# samd21g_board.net
KiCad netlist of a schematic drawn in EAGLE
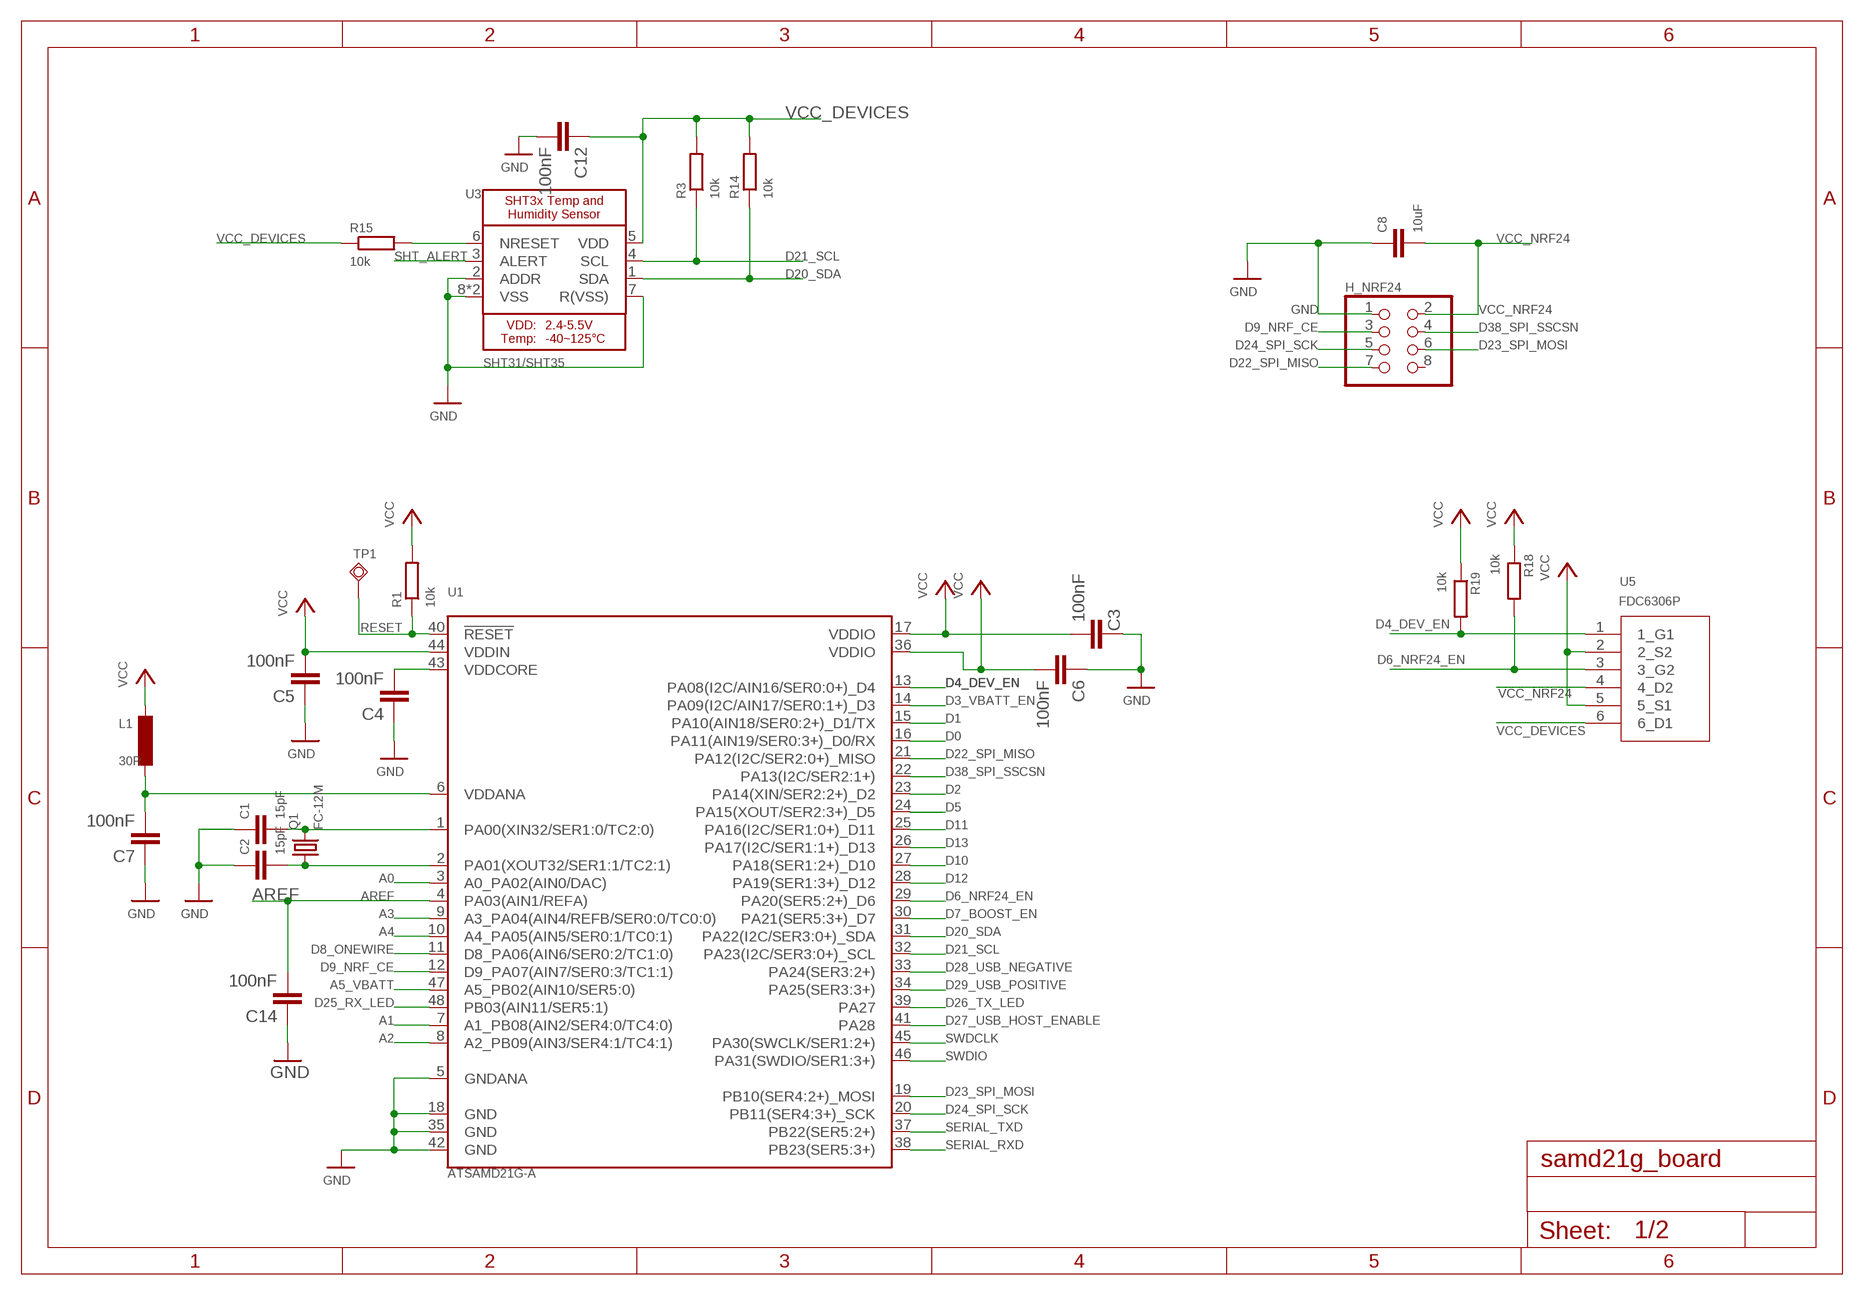
[diagram p0: schematic, sheet 1]
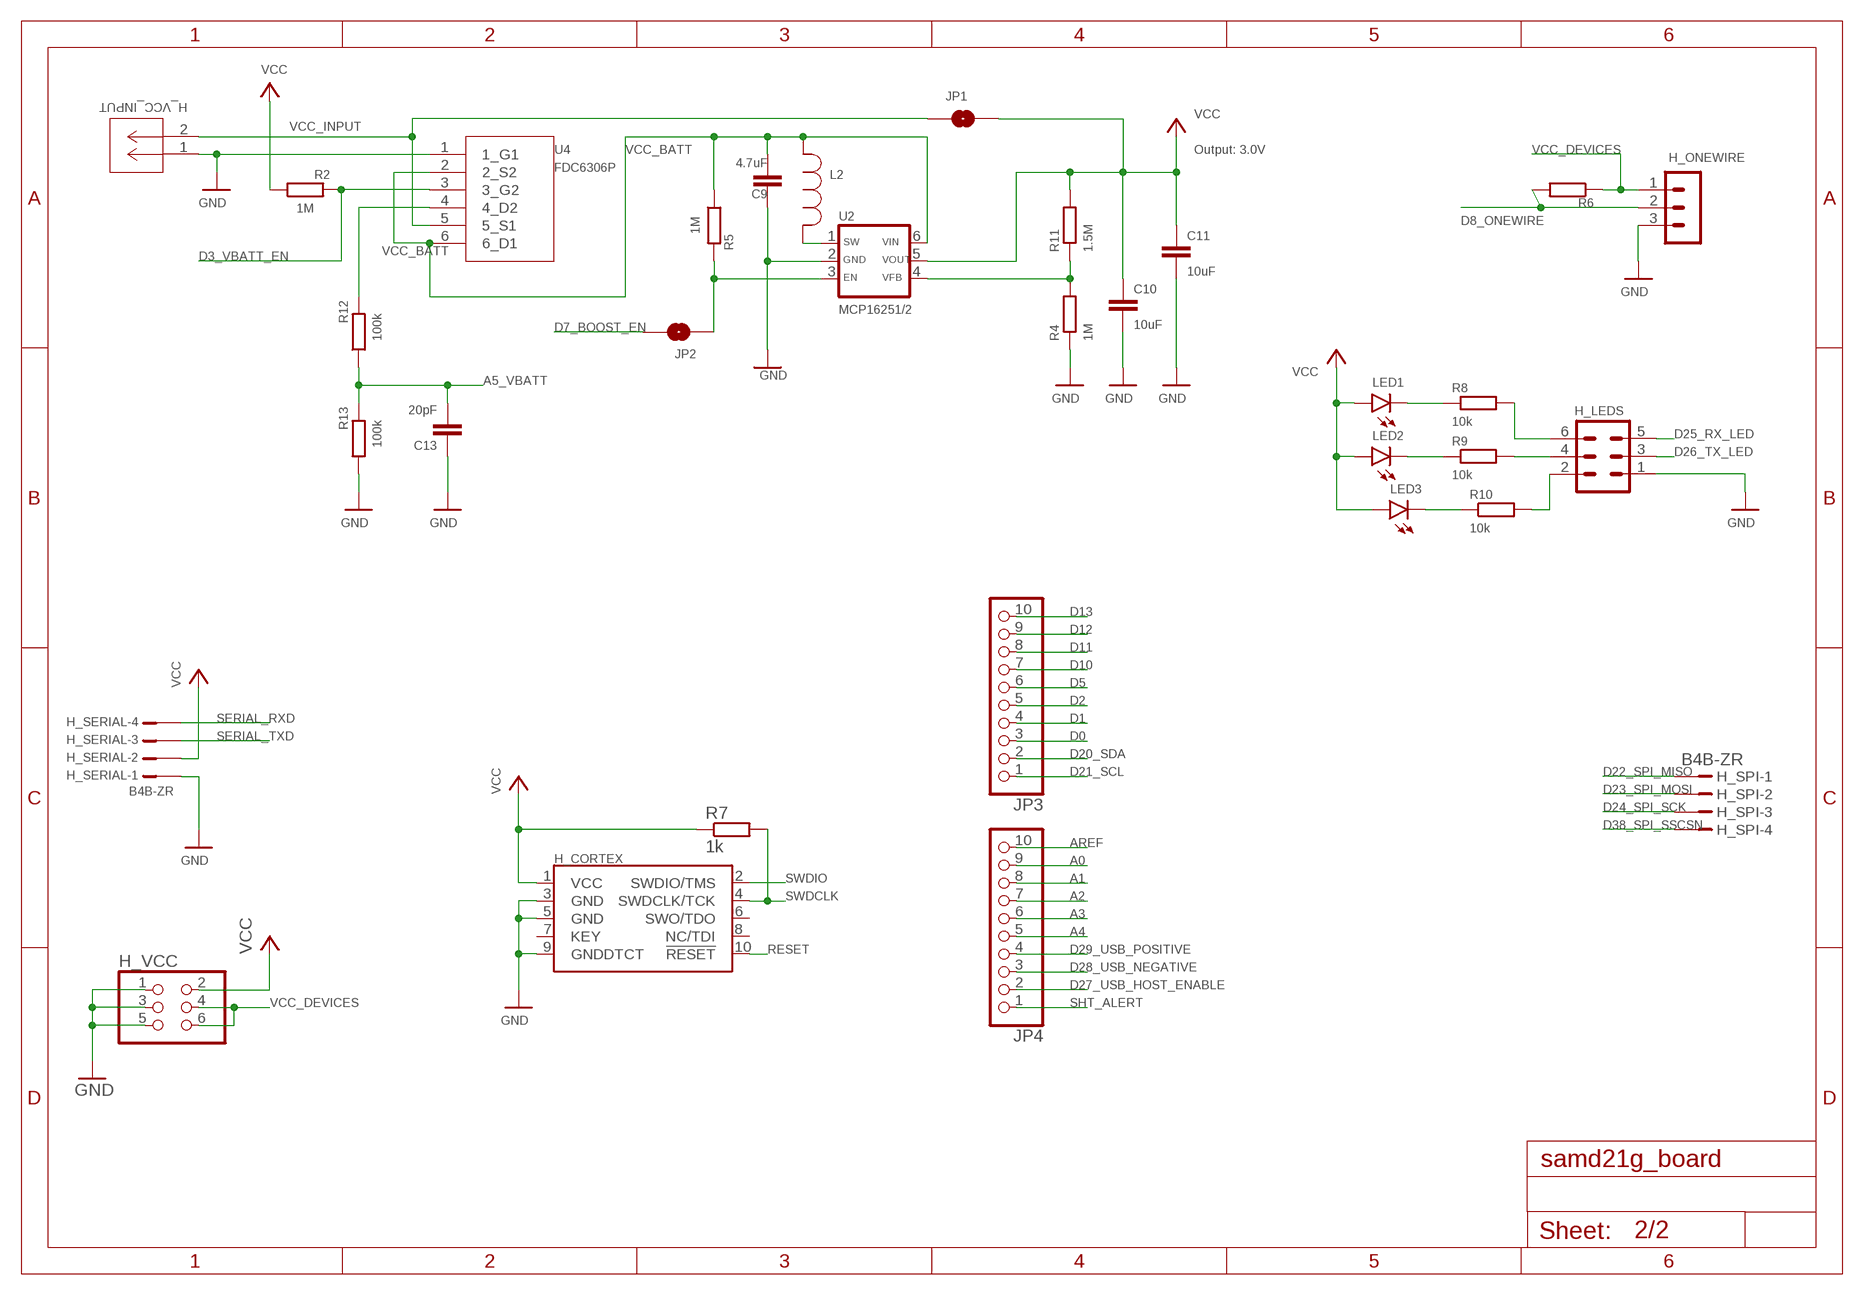
[diagram p1: schematic, sheet 2]

(export (version "E")
  (design (tool "Eeschema 10.0.6"))
  (components
    (comp (ref "C1")
      (value "15pF")
      (footprint "eagle-import:C0402")
      (libsource (lib "eagle-import") (part "C-EUC0402"))
    )
    (comp (ref "C2")
      (value "15pF")
      (footprint "eagle-import:C0402")
      (libsource (lib "eagle-import") (part "C-EUC0402"))
    )
    (comp (ref "C3")
      (value "100nF")
      (footprint "eagle-import:C0603")
      (libsource (lib "eagle-import") (part "C-EUC0603"))
    )
    (comp (ref "C4")
      (value "100nF")
      (footprint "eagle-import:C0603")
      (libsource (lib "eagle-import") (part "C-EUC0603"))
    )
    (comp (ref "C5")
      (value "100nF")
      (footprint "eagle-import:C0603")
      (libsource (lib "eagle-import") (part "C-EUC0603"))
    )
    (comp (ref "C6")
      (value "100nF")
      (footprint "eagle-import:C0603")
      (libsource (lib "eagle-import") (part "C-EUC0603"))
    )
    (comp (ref "C7")
      (value "100nF")
      (footprint "eagle-import:C0603")
      (libsource (lib "eagle-import") (part "C-EUC0603"))
    )
    (comp (ref "C8")
      (value "10uF")
      (footprint "eagle-import:C0805")
      (libsource (lib "eagle-import") (part "C-EUC0805"))
    )
    (comp (ref "C12")
      (value "100nF")
      (footprint "eagle-import:C0603")
      (libsource (lib "eagle-import") (part "C-EUC0603"))
    )
    (comp (ref "C14")
      (value "100nF")
      (footprint "eagle-import:C0603")
      (libsource (lib "eagle-import") (part "C-EUC0603"))
    )
    (comp (ref "H_NRF24")
      (value "PINHD-2X04_2.54")
      (footprint "eagle-import:2X04")
      (libsource (lib "eagle-import") (part "PINHD-2X04_2.54"))
    )
    (comp (ref "L1")
      (value "30R")
      (footprint "eagle-import:L3225M")
      (libsource (lib "eagle-import") (part "L-EUL3225M"))
    )
    (comp (ref "Q1")
      (value "FC-12M")
      (footprint "eagle-import:FC-12M")
      (libsource (lib "eagle-import") (part "FC-12M"))
    )
    (comp (ref "R1")
      (value "10k")
      (footprint "eagle-import:R0805")
      (libsource (lib "eagle-import") (part "R-EU_R0805"))
    )
    (comp (ref "R3")
      (value "10k")
      (footprint "eagle-import:R0805")
      (libsource (lib "eagle-import") (part "R-EU_R0805"))
    )
    (comp (ref "R14")
      (value "10k")
      (footprint "eagle-import:R0805")
      (libsource (lib "eagle-import") (part "R-EU_R0805"))
    )
    (comp (ref "R15")
      (value "10k")
      (footprint "eagle-import:R0805")
      (libsource (lib "eagle-import") (part "R-EU_R0805"))
    )
    (comp (ref "R18")
      (value "10k")
      (footprint "eagle-import:R0805")
      (libsource (lib "eagle-import") (part "R-EU_R0805"))
    )
    (comp (ref "R19")
      (value "10k")
      (footprint "eagle-import:R0805")
      (libsource (lib "eagle-import") (part "R-EU_R0805"))
    )
    (comp (ref "TP1")
      (value "TPSQTP13SQ")
      (footprint "eagle-import:TP13SQ")
      (libsource (lib "eagle-import") (part "TPSQTP13SQ"))
    )
    (comp (ref "U1")
      (value "ATSAMD21G-A")
      (footprint "eagle-import:TQFP-48")
      (libsource (lib "eagle-import") (part "ATSAMD21G-A"))
    )
    (comp (ref "U3")
      (value "SHT31/SHT35")
      (footprint "eagle-import:SHT3X_DFN8")
      (libsource (lib "eagle-import") (part "SHT3X"))
    )
    (comp (ref "U5")
      (value "FDC6306P")
      (footprint "eagle-import:TSOT23-6_419BL_ONS")
      (fields (field (name "COPYRIGHT") "Copyright (C) 2018 Accelerated Designs. All rights reserved"))
      (libsource (lib "eagle-import") (part "FDC6306P"))
    )
    (comp (ref "C9")
      (value "4.7uF")
      (footprint "eagle-import:C0805")
      (libsource (lib "eagle-import") (part "C-EUC0805"))
    )
    (comp (ref "C10")
      (value "10uF")
      (footprint "eagle-import:C0805")
      (libsource (lib "eagle-import") (part "C-EUC0805"))
    )
    (comp (ref "C11")
      (value "10uF")
      (footprint "eagle-import:C0805")
      (libsource (lib "eagle-import") (part "C-EUC0805"))
    )
    (comp (ref "C13")
      (value "20pF")
      (footprint "eagle-import:C0402")
      (libsource (lib "eagle-import") (part "C-EUC0402"))
    )
    (comp (ref "H_CORTEX")
      (value "CORTEX_JTAG_DEBUG_PTH")
      (footprint "eagle-import:2X5-PTH-1.27MM")
      (fields (field (name "SPICEPREFIX") "X"))
      (libsource (lib "eagle-import") (part "CORTEX_JTAG_DEBUG_PTH"))
    )
    (comp (ref "H_LEDS")
      (value "M_2R03_50MIL-V2")
      (footprint "eagle-import:M_2R03_50MIL-V2")
      (libsource (lib "eagle-import") (part "M_2R03_50MIL-V2"))
    )
    (comp (ref "H_ONEWIRE")
      (value "M_1R03_50MIL-V")
      (footprint "eagle-import:M_1R03_50MIL-V")
      (libsource (lib "eagle-import") (part "M_1R03_50MIL-V"))
    )
    (comp (ref "H_SERIAL")
      (value "B4B-ZR")
      (footprint "eagle-import:B4B-ZR")
      (fields (field (name "MF") "FARNELL") (field (name "MPN") "B4B-ZR(LF)(SN)"))
      (libsource (lib "eagle-import") (part "?4B-ZRB"))
    )
    (comp (ref "H_SPI")
      (value "B4B-ZR")
      (footprint "eagle-import:B4B-ZR")
      (fields (field (name "MF") "FARNELL") (field (name "MPN") "B4B-ZR(LF)(SN)"))
      (libsource (lib "eagle-import") (part "?4B-ZRB"))
    )
    (comp (ref "H_VCC")
      (value "PINHD-2X03_2.54")
      (footprint "eagle-import:2X03")
      (libsource (lib "eagle-import") (part "PINHD-2X03_2.54"))
    )
    (comp (ref "H_VCC_INPUT")
      (value "S2B-ZR")
      (footprint "eagle-import:CONN_S2B-ZR_JST")
      (fields
        (field (name "MANUFACTURER_PART_NUMBER") "S2B-ZR(LF)(SN)")
        (field (name "COPYRIGHT") "Copyright (C) 2018 Accelerated Designs. All rights reserved")
      )
      (libsource (lib "eagle-import") (part "S2B-ZR(LF)(SN)"))
    )
    (comp (ref "JP1")
      (value "JUMPER-SMT_2_NO_NO-SILK")
      (footprint "eagle-import:SMT-JUMPER_2_NO_NO-SILK")
      (libsource (lib "eagle-import") (part "JUMPER-SMT_2_NO_NO-SILK"))
    )
    (comp (ref "JP2")
      (value "JUMPER-SMT_2_NO_NO-SILK")
      (footprint "eagle-import:SMT-JUMPER_2_NO_NO-SILK")
      (libsource (lib "eagle-import") (part "JUMPER-SMT_2_NO_NO-SILK"))
    )
    (comp (ref "JP3")
      (value "PINHD-1X10_2.54-S")
      (footprint "eagle-import:1X10-S")
      (libsource (lib "eagle-import") (part "PINHD-1X10_2.54-S"))
    )
    (comp (ref "JP4")
      (value "PINHD-1X10_2.54-S")
      (footprint "eagle-import:1X10-S")
      (libsource (lib "eagle-import") (part "PINHD-1X10_2.54-S"))
    )
    (comp (ref "L2")
      (value "4.7uH")
      (footprint "eagle-import:IND_CDRH3D16-4R7NC_SUM")
      (fields
        (field (name "MANUFACTURER_PART_NUMBER") "CDRH3D16/HPNP-4R7NC")
        (field (name "COPYRIGHT") "Copyright (C) 2018 Accelerated Designs. All rights reserved")
      )
      (libsource (lib "eagle-import") (part "CDRH3D16-4R7NC"))
    )
    (comp (ref "LED1")
      (value "LEDCHIP-LED0805")
      (footprint "eagle-import:CHIP-LED0805")
      (libsource (lib "eagle-import") (part "LEDCHIP-LED0805"))
    )
    (comp (ref "LED2")
      (value "LEDCHIP-LED0805")
      (footprint "eagle-import:CHIP-LED0805")
      (libsource (lib "eagle-import") (part "LEDCHIP-LED0805"))
    )
    (comp (ref "LED3")
      (value "LEDCHIP-LED0805")
      (footprint "eagle-import:CHIP-LED0805")
      (libsource (lib "eagle-import") (part "LEDCHIP-LED0805"))
    )
    (comp (ref "R2")
      (value "1M")
      (footprint "eagle-import:R0805")
      (libsource (lib "eagle-import") (part "R-EU_R0805"))
    )
    (comp (ref "R4")
      (value "1M")
      (footprint "eagle-import:R0805")
      (libsource (lib "eagle-import") (part "R-EU_R0805"))
    )
    (comp (ref "R5")
      (value "1M")
      (footprint "eagle-import:R0805")
      (libsource (lib "eagle-import") (part "R-EU_R0805"))
    )
    (comp (ref "R6")
      (value "4.7k")
      (footprint "eagle-import:R0805")
      (libsource (lib "eagle-import") (part "R-EU_R0805"))
    )
    (comp (ref "R7")
      (value "1k")
      (footprint "eagle-import:R0805")
      (fields (field (name "SPICEPREFIX") "R"))
      (libsource (lib "eagle-import") (part "R-EU_R0805"))
    )
    (comp (ref "R8")
      (value "10k")
      (footprint "eagle-import:R0805")
      (libsource (lib "eagle-import") (part "R-EU_R0805"))
    )
    (comp (ref "R9")
      (value "10k")
      (footprint "eagle-import:R0805")
      (libsource (lib "eagle-import") (part "R-EU_R0805"))
    )
    (comp (ref "R10")
      (value "10k")
      (footprint "eagle-import:R0805")
      (libsource (lib "eagle-import") (part "R-EU_R0805"))
    )
    (comp (ref "R11")
      (value "1.5M")
      (footprint "eagle-import:R0805")
      (libsource (lib "eagle-import") (part "R-EU_R0805"))
    )
    (comp (ref "R12")
      (value "100k")
      (footprint "eagle-import:R0805")
      (libsource (lib "eagle-import") (part "R-EU_R0805"))
    )
    (comp (ref "R13")
      (value "100k")
      (footprint "eagle-import:R0805")
      (libsource (lib "eagle-import") (part "R-EU_R0805"))
    )
    (comp (ref "U2")
      (value "MCP16251/2")
      (footprint "eagle-import:SOT-23-6")
      (libsource (lib "eagle-import") (part "MCP16251/2"))
    )
    (comp (ref "U4")
      (value "FDC6306P")
      (footprint "eagle-import:TSOT23-6_419BL_ONS")
      (fields (field (name "COPYRIGHT") "Copyright (C) 2018 Accelerated Designs. All rights reserved"))
      (libsource (lib "eagle-import") (part "FDC6306P"))
    )
  )
  (nets
    (net (code "1") (name "A0") (class "Default")
      (node (ref "JP4") (pin "9") (pinfunction "9_9") (pintype "passive"))
      (node (ref "U1") (pin "3") (pinfunction "A0_PA02(AIN0/DAC)_3") (pintype "bidirectional"))
    )
    (net (code "2") (name "A1") (class "Default")
      (node (ref "JP4") (pin "8") (pinfunction "8_8") (pintype "passive"))
      (node (ref "U1") (pin "7") (pinfunction "A1_PB08(AIN2/SER4:0/TC4:0)_7") (pintype "bidirectional"))
    )
    (net (code "3") (name "A2") (class "Default")
      (node (ref "JP4") (pin "7") (pinfunction "7_7") (pintype "passive"))
      (node (ref "U1") (pin "8") (pinfunction "A2_PB09(AIN3/SER4:1/TC4:1)_8") (pintype "bidirectional"))
    )
    (net (code "4") (name "A3") (class "Default")
      (node (ref "JP4") (pin "6") (pinfunction "6_6") (pintype "passive"))
      (node (ref "U1") (pin "9") (pinfunction "A3_PA04(AIN4/REFB/SER0:0/TC0:0)_9") (pintype "bidirectional"))
    )
    (net (code "5") (name "A4") (class "Default")
      (node (ref "JP4") (pin "5") (pinfunction "5_5") (pintype "passive"))
      (node (ref "U1") (pin "10") (pinfunction "A4_PA05(AIN5/SER0:1/TC0:1)_10") (pintype "bidirectional"))
    )
    (net (code "6") (name "A5_VBATT") (class "Default")
      (node (ref "C13") (pin "2") (pinfunction "2_2") (pintype "passive"))
      (node (ref "R12") (pin "1") (pinfunction "1_1") (pintype "passive"))
      (node (ref "R13") (pin "2") (pinfunction "2_2") (pintype "passive"))
      (node (ref "U1") (pin "47") (pinfunction "A5_PB02(AIN10/SER5:0)_47") (pintype "bidirectional"))
    )
    (net (code "7") (name "AREF") (class "Default")
      (node (ref "C14") (pin "2") (pinfunction "2_2") (pintype "passive"))
      (node (ref "JP4") (pin "10") (pinfunction "10_10") (pintype "passive"))
      (node (ref "U1") (pin "4") (pinfunction "PA03(AIN1/REFA)_4") (pintype "bidirectional"))
    )
    (net (code "8") (name "D0") (class "Default")
      (node (ref "JP3") (pin "3") (pinfunction "3_3") (pintype "passive"))
      (node (ref "U1") (pin "16") (pinfunction "PA11(AIN19/SER0:3+)_D0/RX_16") (pintype "bidirectional"))
    )
    (net (code "9") (name "D1") (class "Default")
      (node (ref "JP3") (pin "4") (pinfunction "4_4") (pintype "passive"))
      (node (ref "U1") (pin "15") (pinfunction "PA10(AIN18/SER0:2+)_D1/TX_15") (pintype "bidirectional"))
    )
    (net (code "10") (name "D2") (class "Default")
      (node (ref "JP3") (pin "5") (pinfunction "5_5") (pintype "passive"))
      (node (ref "U1") (pin "23") (pinfunction "PA14(XIN/SER2:2+)_D2_23") (pintype "bidirectional"))
    )
    (net (code "11") (name "D3_VBATT_EN") (class "Default")
      (node (ref "R2") (pin "2") (pinfunction "2_2") (pintype "passive"))
      (node (ref "U1") (pin "14") (pinfunction "PA09(I2C/AIN17/SER0:1+)_D3_14") (pintype "bidirectional"))
      (node (ref "U4") (pin "3") (pinfunction "3_G2_3") (pintype "passive"))
    )
    (net (code "12") (name "D4_DEV_EN") (class "Default")
      (node (ref "R19") (pin "2") (pinfunction "2_2") (pintype "passive"))
      (node (ref "U1") (pin "13") (pinfunction "PA08(I2C/AIN16/SER0:0+)_D4_13") (pintype "bidirectional"))
      (node (ref "U5") (pin "1") (pinfunction "1_G1_1") (pintype "passive"))
    )
    (net (code "13") (name "D5") (class "Default")
      (node (ref "JP3") (pin "6") (pinfunction "6_6") (pintype "passive"))
      (node (ref "U1") (pin "24") (pinfunction "PA15(XOUT/SER2:3+)_D5_24") (pintype "bidirectional"))
    )
    (net (code "14") (name "D6_NRF24_EN") (class "Default")
      (node (ref "R18") (pin "2") (pinfunction "2_2") (pintype "passive"))
      (node (ref "U1") (pin "29") (pinfunction "PA20(SER5:2+)_D6_29") (pintype "bidirectional"))
      (node (ref "U5") (pin "3") (pinfunction "3_G2_3") (pintype "passive"))
    )
    (net (code "15") (name "D7_BOOST_EN") (class "Default")
      (node (ref "JP2") (pin "2") (pinfunction "2_2") (pintype "passive"))
      (node (ref "U1") (pin "30") (pinfunction "PA21(SER5:3+)_D7_30") (pintype "bidirectional"))
    )
    (net (code "16") (name "D8_ONEWIRE") (class "Default")
      (node (ref "H_ONEWIRE") (pin "2") (pinfunction "2_2") (pintype "bidirectional"))
      (node (ref "R6") (pin "2") (pinfunction "2_2") (pintype "passive"))
      (node (ref "U1") (pin "11") (pinfunction "D8_PA06(AIN6/SER0:2/TC1:0)_11") (pintype "bidirectional"))
    )
    (net (code "17") (name "D9_NRF_CE") (class "Default")
      (node (ref "H_NRF24") (pin "3") (pinfunction "3_3") (pintype "passive"))
      (node (ref "U1") (pin "12") (pinfunction "D9_PA07(AIN7/SER0:3/TC1:1)_12") (pintype "bidirectional"))
    )
    (net (code "18") (name "D10") (class "Default")
      (node (ref "JP3") (pin "7") (pinfunction "7_7") (pintype "passive"))
      (node (ref "U1") (pin "27") (pinfunction "PA18(SER1:2+)_D10_27") (pintype "bidirectional"))
    )
    (net (code "19") (name "D11") (class "Default")
      (node (ref "JP3") (pin "8") (pinfunction "8_8") (pintype "passive"))
      (node (ref "U1") (pin "25") (pinfunction "PA16(I2C/SER1:0+)_D11_25") (pintype "bidirectional"))
    )
    (net (code "20") (name "D12") (class "Default")
      (node (ref "JP3") (pin "9") (pinfunction "9_9") (pintype "passive"))
      (node (ref "U1") (pin "28") (pinfunction "PA19(SER1:3+)_D12_28") (pintype "bidirectional"))
    )
    (net (code "21") (name "D13") (class "Default")
      (node (ref "JP3") (pin "10") (pinfunction "10_10") (pintype "passive"))
      (node (ref "U1") (pin "26") (pinfunction "PA17(I2C/SER1:1+)_D13_26") (pintype "bidirectional"))
    )
    (net (code "22") (name "D20_SDA") (class "Default")
      (node (ref "JP3") (pin "2") (pinfunction "2_2") (pintype "passive"))
      (node (ref "R14") (pin "1") (pinfunction "1_1") (pintype "passive"))
      (node (ref "U1") (pin "31") (pinfunction "PA22(I2C/SER3:0+)_SDA_31") (pintype "bidirectional"))
      (node (ref "U3") (pin "1") (pinfunction "SDA_1") (pintype "bidirectional"))
    )
    (net (code "23") (name "D21_SCL") (class "Default")
      (node (ref "JP3") (pin "1") (pinfunction "1_1") (pintype "passive"))
      (node (ref "R3") (pin "1") (pinfunction "1_1") (pintype "passive"))
      (node (ref "U1") (pin "32") (pinfunction "PA23(I2C/SER3:0+)_SCL_32") (pintype "bidirectional"))
      (node (ref "U3") (pin "4") (pinfunction "SCL_4") (pintype "bidirectional"))
    )
    (net (code "24") (name "D22_SPI_MISO") (class "Default")
      (node (ref "H_NRF24") (pin "7") (pinfunction "7_7") (pintype "passive"))
      (node (ref "H_SPI") (pin "1") (pinfunction "1_1") (pintype "passive"))
      (node (ref "U1") (pin "21") (pinfunction "PA12(I2C/SER2:0+)_MISO_21") (pintype "bidirectional"))
    )
    (net (code "25") (name "D23_SPI_MOSI") (class "Default")
      (node (ref "H_NRF24") (pin "6") (pinfunction "6_6") (pintype "passive"))
      (node (ref "H_SPI") (pin "2") (pinfunction "1_2") (pintype "passive"))
      (node (ref "U1") (pin "19") (pinfunction "PB10(SER4:2+)_MOSI_19") (pintype "bidirectional"))
    )
    (net (code "26") (name "D24_SPI_SCK") (class "Default")
      (node (ref "H_NRF24") (pin "5") (pinfunction "5_5") (pintype "passive"))
      (node (ref "H_SPI") (pin "3") (pinfunction "1_3") (pintype "passive"))
      (node (ref "U1") (pin "20") (pinfunction "PB11(SER4:3+)_SCK_20") (pintype "bidirectional"))
    )
    (net (code "27") (name "D25_RX_LED") (class "Default")
      (node (ref "H_LEDS") (pin "5") (pinfunction "5_5") (pintype "bidirectional"))
      (node (ref "U1") (pin "48") (pinfunction "PB03(AIN11/SER5:1)_48") (pintype "bidirectional"))
    )
    (net (code "28") (name "D26_TX_LED") (class "Default")
      (node (ref "H_LEDS") (pin "3") (pinfunction "3_3") (pintype "bidirectional"))
      (node (ref "U1") (pin "39") (pinfunction "PA27_39") (pintype "bidirectional"))
    )
    (net (code "29") (name "D27_USB_HOST_ENABLE") (class "Default")
      (node (ref "JP4") (pin "2") (pinfunction "2_2") (pintype "passive"))
      (node (ref "U1") (pin "41") (pinfunction "PA28_41") (pintype "bidirectional"))
    )
    (net (code "30") (name "D28_USB_NEGATIVE") (class "Default")
      (node (ref "JP4") (pin "3") (pinfunction "3_3") (pintype "passive"))
      (node (ref "U1") (pin "33") (pinfunction "PA24(SER3:2+)_33") (pintype "bidirectional"))
    )
    (net (code "31") (name "D29_USB_POSITIVE") (class "Default")
      (node (ref "JP4") (pin "4") (pinfunction "4_4") (pintype "passive"))
      (node (ref "U1") (pin "34") (pinfunction "PA25(SER3:3+)_34") (pintype "bidirectional"))
    )
    (net (code "32") (name "D38_SPI_SSCSN") (class "Default")
      (node (ref "H_NRF24") (pin "4") (pinfunction "4_4") (pintype "passive"))
      (node (ref "H_SPI") (pin "4") (pinfunction "1_4") (pintype "passive"))
      (node (ref "U1") (pin "22") (pinfunction "PA13(I2C/SER2:1+)_22") (pintype "bidirectional"))
    )
    (net (code "33") (name "GND") (class "Default")
      (node (ref "C1") (pin "1") (pinfunction "1_1") (pintype "passive"))
      (node (ref "C10") (pin "2") (pinfunction "2_2") (pintype "passive"))
      (node (ref "C11") (pin "2") (pinfunction "2_2") (pintype "passive"))
      (node (ref "C12") (pin "2") (pinfunction "2_2") (pintype "passive"))
      (node (ref "C13") (pin "1") (pinfunction "1_1") (pintype "passive"))
      (node (ref "C14") (pin "1") (pinfunction "1_1") (pintype "passive"))
      (node (ref "C2") (pin "1") (pinfunction "1_1") (pintype "passive"))
      (node (ref "C3") (pin "1") (pinfunction "1_1") (pintype "passive"))
      (node (ref "C4") (pin "1") (pinfunction "1_1") (pintype "passive"))
      (node (ref "C5") (pin "1") (pinfunction "1_1") (pintype "passive"))
      (node (ref "C6") (pin "1") (pinfunction "1_1") (pintype "passive"))
      (node (ref "C7") (pin "1") (pinfunction "1_1") (pintype "passive"))
      (node (ref "C8") (pin "1") (pinfunction "1_1") (pintype "passive"))
      (node (ref "C9") (pin "1") (pinfunction "1_1") (pintype "passive"))
      (node (ref "H_CORTEX") (pin "3") (pinfunction "GND_3") (pintype "bidirectional"))
      (node (ref "H_CORTEX") (pin "5") (pinfunction "GND_5") (pintype "bidirectional"))
      (node (ref "H_CORTEX") (pin "9") (pinfunction "GNDDTCT_9") (pintype "bidirectional"))
      (node (ref "H_LEDS") (pin "1") (pinfunction "1_1") (pintype "bidirectional"))
      (node (ref "H_NRF24") (pin "1") (pinfunction "1_1") (pintype "passive"))
      (node (ref "H_ONEWIRE") (pin "3") (pinfunction "3_3") (pintype "bidirectional"))
      (node (ref "H_SERIAL") (pin "1") (pinfunction "1_1") (pintype "passive"))
      (node (ref "H_VCC") (pin "1") (pinfunction "1_1") (pintype "passive"))
      (node (ref "H_VCC") (pin "3") (pinfunction "3_3") (pintype "passive"))
      (node (ref "H_VCC") (pin "5") (pinfunction "5_5") (pintype "passive"))
      (node (ref "H_VCC_INPUT") (pin "1") (pinfunction "1_1") (pintype "passive"))
      (node (ref "R13") (pin "1") (pinfunction "1_1") (pintype "passive"))
      (node (ref "R4") (pin "1") (pinfunction "1_1") (pintype "passive"))
      (node (ref "U1") (pin "18") (pinfunction "GND_18") (pintype "bidirectional"))
      (node (ref "U1") (pin "35") (pinfunction "GND_35") (pintype "bidirectional"))
      (node (ref "U1") (pin "42") (pinfunction "GND_42") (pintype "bidirectional"))
      (node (ref "U1") (pin "5") (pinfunction "GNDANA_5") (pintype "bidirectional"))
      (node (ref "U2") (pin "2") (pinfunction "GND_2") (pintype "passive"))
      (node (ref "U3") (pin "2") (pinfunction "ADDR_2") (pintype "bidirectional"))
      (node (ref "U3") (pin "7") (pinfunction "R(VSS)_7") (pintype "bidirectional"))
      (node (ref "U3") (pin "8") (pinfunction "VSS_8") (pintype "power_in"))
      (node (ref "U3") (pin "THERMAL") (pinfunction "VSS_THERMAL") (pintype "power_in"))
      (node (ref "U4") (pin "1") (pinfunction "1_G1_1") (pintype "passive"))
    )
    (net (code "34") (name "Net-(H_LEDS-Pad2)") (class "Default")
      (node (ref "H_LEDS") (pin "2") (pinfunction "2_2") (pintype "bidirectional"))
      (node (ref "R10") (pin "2") (pinfunction "2_2") (pintype "passive"))
    )
    (net (code "35") (name "Net-(H_LEDS-Pad4)") (class "Default")
      (node (ref "H_LEDS") (pin "4") (pinfunction "4_4") (pintype "bidirectional"))
      (node (ref "R9") (pin "2") (pinfunction "2_2") (pintype "passive"))
    )
    (net (code "36") (name "Net-(H_LEDS-Pad6)") (class "Default")
      (node (ref "H_LEDS") (pin "6") (pinfunction "6_6") (pintype "bidirectional"))
      (node (ref "R8") (pin "2") (pinfunction "2_2") (pintype "passive"))
    )
    (net (code "37") (name "Net-(LED1-PadC)") (class "Default")
      (node (ref "LED1") (pin "C") (pinfunction "C_C") (pintype "passive"))
      (node (ref "R8") (pin "1") (pinfunction "1_1") (pintype "passive"))
    )
    (net (code "38") (name "Net-(LED2-PadC)") (class "Default")
      (node (ref "LED2") (pin "C") (pinfunction "C_C") (pintype "passive"))
      (node (ref "R9") (pin "1") (pinfunction "1_1") (pintype "passive"))
    )
    (net (code "39") (name "Net-(LED3-PadC)") (class "Default")
      (node (ref "LED3") (pin "C") (pinfunction "C_C") (pintype "passive"))
      (node (ref "R10") (pin "1") (pinfunction "1_1") (pintype "passive"))
    )
    (net (code "40") (name "Net-(U1-PA00(XIN32{slash}SER1:0{slash}TC2:0))") (class "Default")
      (node (ref "C1") (pin "2") (pinfunction "2_2") (pintype "passive"))
      (node (ref "Q1") (pin "2") (pinfunction "2_2") (pintype "passive"))
      (node (ref "U1") (pin "1") (pinfunction "PA00(XIN32/SER1:0/TC2:0)_1") (pintype "bidirectional"))
    )
    (net (code "41") (name "Net-(U1-PA01(XOUT32{slash}SER1:1{slash}TC2:1))") (class "Default")
      (node (ref "C2") (pin "2") (pinfunction "2_2") (pintype "passive"))
      (node (ref "Q1") (pin "1") (pinfunction "1_1") (pintype "passive"))
      (node (ref "U1") (pin "2") (pinfunction "PA01(XOUT32/SER1:1/TC2:1)_2") (pintype "bidirectional"))
    )
    (net (code "42") (name "Net-(U1-VDDANA)") (class "Default")
      (node (ref "C7") (pin "2") (pinfunction "2_2") (pintype "passive"))
      (node (ref "L1") (pin "2") (pinfunction "2_2") (pintype "passive"))
      (node (ref "U1") (pin "6") (pinfunction "VDDANA_6") (pintype "bidirectional"))
    )
    (net (code "43") (name "Net-(U1-VDDCORE)") (class "Default")
      (node (ref "C4") (pin "2") (pinfunction "2_2") (pintype "passive"))
      (node (ref "U1") (pin "43") (pinfunction "VDDCORE_43") (pintype "bidirectional"))
    )
    (net (code "44") (name "Net-(U2-EN)") (class "Default")
      (node (ref "JP2") (pin "1") (pinfunction "1_1") (pintype "passive"))
      (node (ref "R5") (pin "2") (pinfunction "2_2") (pintype "passive"))
      (node (ref "U2") (pin "3") (pinfunction "EN_3") (pintype "passive"))
    )
    (net (code "45") (name "Net-(U2-SW)") (class "Default")
      (node (ref "L2") (pin "1") (pinfunction "1_1") (pintype "passive"))
      (node (ref "U2") (pin "1") (pinfunction "SW_1") (pintype "passive"))
    )
    (net (code "46") (name "Net-(U2-VFB)") (class "Default")
      (node (ref "R11") (pin "1") (pinfunction "1_1") (pintype "passive"))
      (node (ref "R4") (pin "2") (pinfunction "2_2") (pintype "passive"))
      (node (ref "U2") (pin "4") (pinfunction "VFB_4") (pintype "passive"))
    )
    (net (code "47") (name "Net-(U3-NRESET)") (class "Default")
      (node (ref "R15") (pin "2") (pinfunction "2_2") (pintype "passive"))
      (node (ref "U3") (pin "6") (pinfunction "NRESET_6") (pintype "bidirectional"))
    )
    (net (code "48") (name "Net-(U4-4_D2)") (class "Default")
      (node (ref "R12") (pin "2") (pinfunction "2_2") (pintype "passive"))
      (node (ref "U4") (pin "4") (pinfunction "4_D2_4") (pintype "passive"))
    )
    (net (code "49") (name "RESET") (class "Default")
      (node (ref "H_CORTEX") (pin "10") (pinfunction "~{RESET}_10") (pintype "bidirectional"))
      (node (ref "R1") (pin "1") (pinfunction "1_1") (pintype "passive"))
      (node (ref "TP1") (pin "TP") (pinfunction "TP_TP") (pintype "input"))
      (node (ref "U1") (pin "40") (pinfunction "~{RESET}_40") (pintype "bidirectional"))
    )
    (net (code "50") (name "SERIAL_RXD") (class "Default")
      (node (ref "H_SERIAL") (pin "4") (pinfunction "1_4") (pintype "passive"))
      (node (ref "U1") (pin "38") (pinfunction "PB23(SER5:3+)_38") (pintype "bidirectional"))
    )
    (net (code "51") (name "SERIAL_TXD") (class "Default")
      (node (ref "H_SERIAL") (pin "3") (pinfunction "1_3") (pintype "passive"))
      (node (ref "U1") (pin "37") (pinfunction "PB22(SER5:2+)_37") (pintype "bidirectional"))
    )
    (net (code "52") (name "SHT_ALERT") (class "Default")
      (node (ref "JP4") (pin "1") (pinfunction "1_1") (pintype "passive"))
      (node (ref "U3") (pin "3") (pinfunction "ALERT_3") (pintype "bidirectional"))
    )
    (net (code "53") (name "SWDCLK") (class "Default")
      (node (ref "H_CORTEX") (pin "4") (pinfunction "SWDCLK/TCK_4") (pintype "bidirectional"))
      (node (ref "R7") (pin "2") (pinfunction "2_2") (pintype "passive"))
      (node (ref "U1") (pin "45") (pinfunction "PA30(SWCLK/SER1:2+)_45") (pintype "bidirectional"))
    )
    (net (code "54") (name "SWDIO") (class "Default")
      (node (ref "H_CORTEX") (pin "2") (pinfunction "SWDIO/TMS_2") (pintype "bidirectional"))
      (node (ref "U1") (pin "46") (pinfunction "PA31(SWDIO/SER1:3+)_46") (pintype "bidirectional"))
    )
    (net (code "55") (name "VCC") (class "Default")
      (node (ref "C10") (pin "1") (pinfunction "1_1") (pintype "passive"))
      (node (ref "C11") (pin "1") (pinfunction "1_1") (pintype "passive"))
      (node (ref "C3") (pin "2") (pinfunction "2_2") (pintype "passive"))
      (node (ref "C5") (pin "2") (pinfunction "2_2") (pintype "passive"))
      (node (ref "C6") (pin "2") (pinfunction "2_2") (pintype "passive"))
      (node (ref "H_CORTEX") (pin "1") (pinfunction "VCC_1") (pintype "bidirectional"))
      (node (ref "H_SERIAL") (pin "2") (pinfunction "1_2") (pintype "passive"))
      (node (ref "H_VCC") (pin "2") (pinfunction "2_2") (pintype "passive"))
      (node (ref "JP1") (pin "2") (pinfunction "2_2") (pintype "passive"))
      (node (ref "L1") (pin "1") (pinfunction "1_1") (pintype "passive"))
      (node (ref "LED1") (pin "A") (pinfunction "A_A") (pintype "passive"))
      (node (ref "LED2") (pin "A") (pinfunction "A_A") (pintype "passive"))
      (node (ref "LED3") (pin "A") (pinfunction "A_A") (pintype "passive"))
      (node (ref "R1") (pin "2") (pinfunction "2_2") (pintype "passive"))
      (node (ref "R11") (pin "2") (pinfunction "2_2") (pintype "passive"))
      (node (ref "R18") (pin "1") (pinfunction "1_1") (pintype "passive"))
      (node (ref "R19") (pin "1") (pinfunction "1_1") (pintype "passive"))
      (node (ref "R2") (pin "1") (pinfunction "1_1") (pintype "passive"))
      (node (ref "R7") (pin "1") (pinfunction "1_1") (pintype "passive"))
      (node (ref "U1") (pin "17") (pinfunction "VDDIO_17") (pintype "bidirectional"))
      (node (ref "U1") (pin "36") (pinfunction "VDDIO_36") (pintype "bidirectional"))
      (node (ref "U1") (pin "44") (pinfunction "VDDIN_44") (pintype "bidirectional"))
      (node (ref "U2") (pin "5") (pinfunction "VOUT_5") (pintype "passive"))
      (node (ref "U5") (pin "2") (pinfunction "2_S2_2") (pintype "passive"))
      (node (ref "U5") (pin "5") (pinfunction "5_S1_5") (pintype "passive"))
    )
    (net (code "56") (name "VCC_BATT") (class "Default")
      (node (ref "C9") (pin "2") (pinfunction "2_2") (pintype "passive"))
      (node (ref "L2") (pin "2") (pinfunction "2_2") (pintype "passive"))
      (node (ref "R5") (pin "1") (pinfunction "1_1") (pintype "passive"))
      (node (ref "U2") (pin "6") (pinfunction "VIN_6") (pintype "passive"))
      (node (ref "U4") (pin "2") (pinfunction "2_S2_2") (pintype "passive"))
      (node (ref "U4") (pin "6") (pinfunction "6_D1_6") (pintype "passive"))
    )
    (net (code "57") (name "VCC_DEVICES") (class "Default")
      (node (ref "C12") (pin "1") (pinfunction "1_1") (pintype "passive"))
      (node (ref "H_ONEWIRE") (pin "1") (pinfunction "1_1") (pintype "bidirectional"))
      (node (ref "H_VCC") (pin "4") (pinfunction "4_4") (pintype "passive"))
      (node (ref "H_VCC") (pin "6") (pinfunction "6_6") (pintype "passive"))
      (node (ref "R14") (pin "2") (pinfunction "2_2") (pintype "passive"))
      (node (ref "R15") (pin "1") (pinfunction "1_1") (pintype "passive"))
      (node (ref "R3") (pin "2") (pinfunction "2_2") (pintype "passive"))
      (node (ref "R6") (pin "1") (pinfunction "1_1") (pintype "passive"))
      (node (ref "U3") (pin "5") (pinfunction "VDD_5") (pintype "power_in"))
      (node (ref "U5") (pin "6") (pinfunction "6_D1_6") (pintype "passive"))
    )
    (net (code "58") (name "VCC_INPUT") (class "Default")
      (node (ref "H_VCC_INPUT") (pin "2") (pinfunction "2_2") (pintype "passive"))
      (node (ref "JP1") (pin "1") (pinfunction "1_1") (pintype "passive"))
      (node (ref "U4") (pin "5") (pinfunction "5_S1_5") (pintype "passive"))
    )
    (net (code "59") (name "VCC_NRF24") (class "Default")
      (node (ref "C8") (pin "2") (pinfunction "2_2") (pintype "passive"))
      (node (ref "H_NRF24") (pin "2") (pinfunction "2_2") (pintype "passive"))
      (node (ref "U5") (pin "4") (pinfunction "4_D2_4") (pintype "passive"))
    )
    (net (code "60") (name "unconnected-(H_CORTEX-KEY-Pad7)") (class "Default")
      (node (ref "H_CORTEX") (pin "7") (pinfunction "KEY_7") (pintype "bidirectional"))
    )
    (net (code "61") (name "unconnected-(H_CORTEX-NC{slash}TDI-Pad8)") (class "Default")
      (node (ref "H_CORTEX") (pin "8") (pinfunction "NC/TDI_8") (pintype "bidirectional"))
    )
    (net (code "62") (name "unconnected-(H_CORTEX-SWO{slash}TDO-Pad6)") (class "Default")
      (node (ref "H_CORTEX") (pin "6") (pinfunction "SWO/TDO_6") (pintype "bidirectional"))
    )
    (net (code "63") (name "unconnected-(H_NRF24-Pad8)") (class "Default")
      (node (ref "H_NRF24") (pin "8") (pinfunction "8_8") (pintype "passive"))
    )
  )
)
